# GaN_FET_Adapter.net
KiCad netlist of a schematic drawn in EAGLE
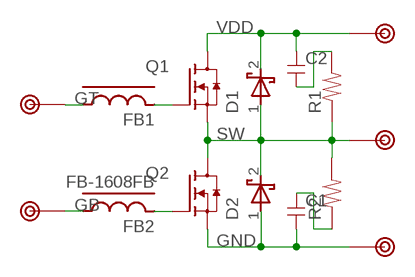
[diagram p0: schematic, sheet 1]

(export (version "E")
  (design (tool "Eeschema 10.0.6"))
  (components
    (comp (ref "C1")
      (value "C-3225-2")
      (footprint "eagle-import:3225-2")
      (libsource (lib "eagle-import") (part "C-3225-2"))
    )
    (comp (ref "C2")
      (value "C-3225-2")
      (footprint "eagle-import:3225-2")
      (libsource (lib "eagle-import") (part "C-3225-2"))
    )
    (comp (ref "D1")
      (value "SBD-1A2")
      (footprint "eagle-import:SOD123")
      (libsource (lib "eagle-import") (part "SBD-1A2"))
    )
    (comp (ref "D2")
      (value "SBD-1A2")
      (footprint "eagle-import:SOD123")
      (libsource (lib "eagle-import") (part "SBD-1A2"))
    )
    (comp (ref "FB1")
      (value "FB-1608FB")
      (footprint "eagle-import:1608-FB")
      (libsource (lib "eagle-import") (part "FB-1608FB"))
    )
    (comp (ref "FB2")
      (value "FB-1608FB")
      (footprint "eagle-import:1608-FB")
      (libsource (lib "eagle-import") (part "FB-1608FB"))
    )
    (comp (ref "Q1")
      (value "NMOS-GAN")
      (footprint "eagle-import:PQFN8X8")
      (libsource (lib "eagle-import") (part "NMOS-GAN"))
    )
    (comp (ref "Q2")
      (value "NMOS-GAN")
      (footprint "eagle-import:PQFN8X8")
      (libsource (lib "eagle-import") (part "NMOS-GAN"))
    )
    (comp (ref "R1")
      (value "R-2012-2")
      (footprint "eagle-import:2012-2")
      (libsource (lib "eagle-import") (part "R-2012-2"))
    )
    (comp (ref "R2")
      (value "R-2012-2")
      (footprint "eagle-import:2012-2")
      (libsource (lib "eagle-import") (part "R-2012-2"))
    )
    (comp (ref "TP1")
      (value "TESTPIN-MID")
      (footprint "eagle-import:TESTPIN-MID")
      (libsource (lib "eagle-import") (part "TESTPIN-MID"))
    )
    (comp (ref "TP2")
      (value "TESTPIN-MID")
      (footprint "eagle-import:TESTPIN-MID")
      (libsource (lib "eagle-import") (part "TESTPIN-MID"))
    )
    (comp (ref "TP3")
      (value "TESTPIN-MID")
      (footprint "eagle-import:TESTPIN-MID")
      (libsource (lib "eagle-import") (part "TESTPIN-MID"))
    )
    (comp (ref "TP4")
      (value "TESTPIN-MID")
      (footprint "eagle-import:TESTPIN-MID")
      (libsource (lib "eagle-import") (part "TESTPIN-MID"))
    )
    (comp (ref "TP5")
      (value "TESTPIN-MID")
      (footprint "eagle-import:TESTPIN-MID")
      (libsource (lib "eagle-import") (part "TESTPIN-MID"))
    )
  )
  (nets
    (net (code "1") (name "/GB") (class "Default")
      (node (ref "FB2") (pin "1") (pinfunction "1_1") (pintype "passive"))
      (node (ref "TP4") (pin "1") (pinfunction "1_1") (pintype "passive"))
    )
    (net (code "2") (name "/GND") (class "Default")
      (node (ref "C1") (pin "2") (pinfunction "2_2") (pintype "passive"))
      (node (ref "D2") (pin "1") (pinfunction "A_1") (pintype "bidirectional"))
      (node (ref "Q2") (pin "S") (pinfunction "S_S") (pintype "passive"))
      (node (ref "TP3") (pin "1") (pinfunction "1_1") (pintype "passive"))
    )
    (net (code "3") (name "/GT") (class "Default")
      (node (ref "FB1") (pin "1") (pinfunction "1_1") (pintype "passive"))
      (node (ref "TP5") (pin "1") (pinfunction "1_1") (pintype "passive"))
    )
    (net (code "4") (name "/SW") (class "Default")
      (node (ref "D1") (pin "1") (pinfunction "A_1") (pintype "bidirectional"))
      (node (ref "D2") (pin "2") (pinfunction "K_2") (pintype "bidirectional"))
      (node (ref "Q1") (pin "S") (pinfunction "S_S") (pintype "passive"))
      (node (ref "Q2") (pin "D") (pinfunction "D_D") (pintype "passive"))
      (node (ref "R1") (pin "1") (pinfunction "1_1") (pintype "passive"))
      (node (ref "R2") (pin "2") (pinfunction "2_2") (pintype "passive"))
      (node (ref "TP2") (pin "1") (pinfunction "1_1") (pintype "passive"))
    )
    (net (code "5") (name "/VDD") (class "Default")
      (node (ref "C2") (pin "1") (pinfunction "1_1") (pintype "passive"))
      (node (ref "D1") (pin "2") (pinfunction "K_2") (pintype "bidirectional"))
      (node (ref "Q1") (pin "D") (pinfunction "D_D") (pintype "passive"))
      (node (ref "TP1") (pin "1") (pinfunction "1_1") (pintype "passive"))
    )
    (net (code "6") (name "Net-(C1-Pad1)") (class "Default")
      (node (ref "C1") (pin "1") (pinfunction "1_1") (pintype "passive"))
      (node (ref "R2") (pin "1") (pinfunction "1_1") (pintype "passive"))
    )
    (net (code "7") (name "Net-(C2-Pad2)") (class "Default")
      (node (ref "C2") (pin "2") (pinfunction "2_2") (pintype "passive"))
      (node (ref "R1") (pin "2") (pinfunction "2_2") (pintype "passive"))
    )
    (net (code "8") (name "Net-(FB1-Pad2)") (class "Default")
      (node (ref "FB1") (pin "2") (pinfunction "2_2") (pintype "passive"))
      (node (ref "Q1") (pin "G") (pinfunction "G_G") (pintype "passive"))
    )
    (net (code "9") (name "Net-(FB2-Pad2)") (class "Default")
      (node (ref "FB2") (pin "2") (pinfunction "2_2") (pintype "passive"))
      (node (ref "Q2") (pin "G") (pinfunction "G_G") (pintype "passive"))
    )
  )
)
